# UsbUartBridge.net
KiCad netlist of a schematic drawn in EAGLE
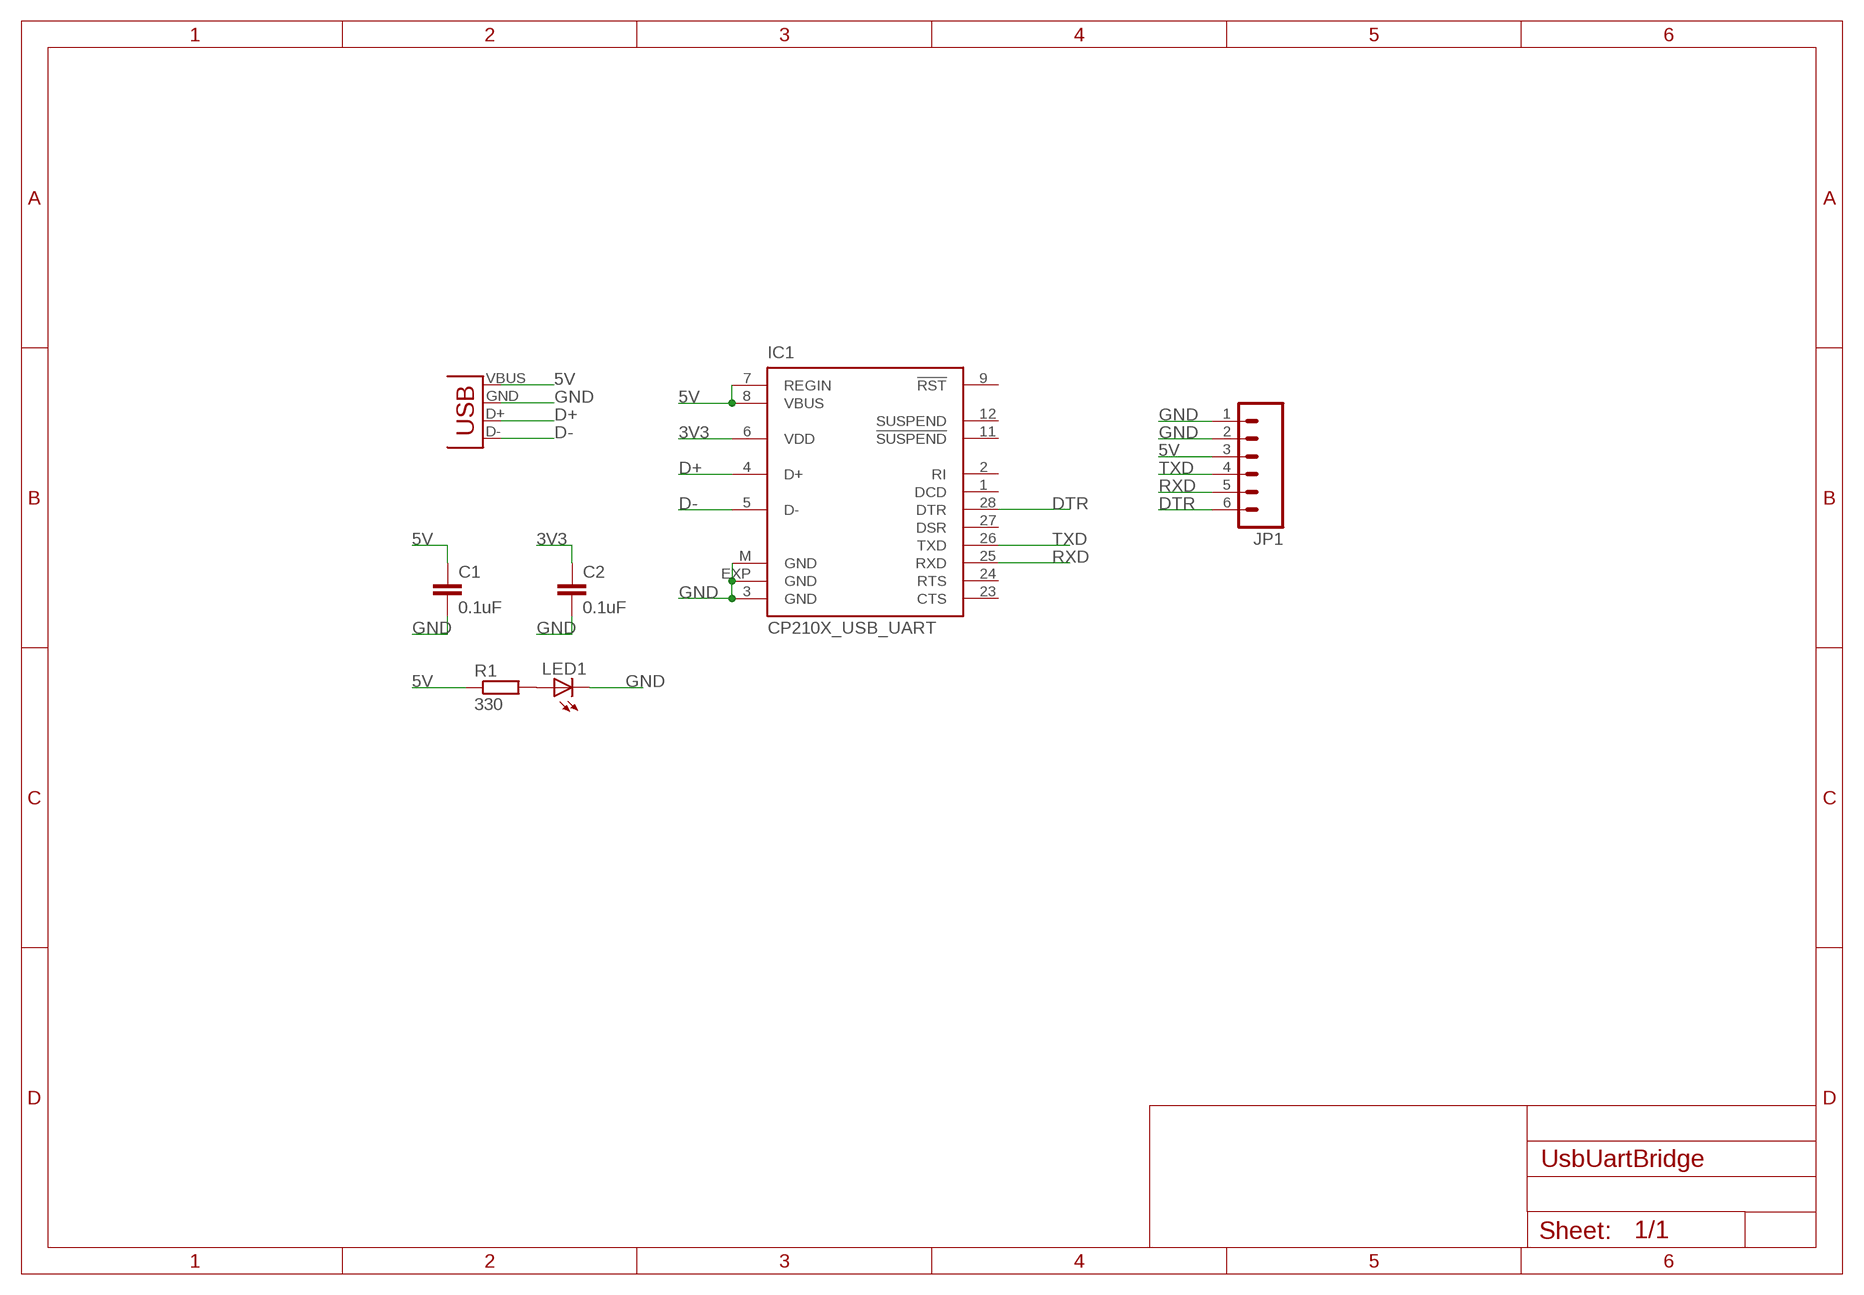
[diagram p0: schematic, sheet 1]

(export (version "E")
  (design (tool "Eeschema 10.0.6"))
  (components
    (comp (ref "C1")
      (value "0.1uF")
      (footprint "eagle-import:C025-024X044")
      (libsource (lib "eagle-import") (part "C-EU025-024X044"))
    )
    (comp (ref "C2")
      (value "0.1uF")
      (footprint "eagle-import:C025-024X044")
      (libsource (lib "eagle-import") (part "C-EU025-024X044"))
    )
    (comp (ref "IC1")
      (value "CP210X_USB_UART")
      (footprint "eagle-import:MLP28")
      (libsource (lib "eagle-import") (part "CP210X_USB_UART"))
    )
    (comp (ref "JP1")
      (value "M06SIP")
      (footprint "eagle-import:1X06")
      (libsource (lib "eagle-import") (part "M06SIP"))
    )
    (comp (ref "LED1")
      (value "LED3MM")
      (footprint "eagle-import:LED3MM")
      (libsource (lib "eagle-import") (part "LED3MM"))
    )
    (comp (ref "R1")
      (value "330")
      (footprint "eagle-import:0204_7")
      (libsource (lib "eagle-import") (part "R-EU_0204/7"))
    )
    (comp (ref "X1")
      (value "USB-A-H")
      (footprint "eagle-import:USB-A-H")
      (libsource (lib "eagle-import") (part "USB-A-H"))
    )
  )
  (nets
    (net (code "1") (name "/3V3") (class "Default")
      (node (ref "C2") (pin "1") (pinfunction "1_1") (pintype "passive"))
      (node (ref "IC1") (pin "6") (pinfunction "VDD_6") (pintype "power_in"))
    )
    (net (code "2") (name "/5V") (class "Default")
      (node (ref "C1") (pin "1") (pinfunction "1_1") (pintype "passive"))
      (node (ref "IC1") (pin "7") (pinfunction "REGIN_7") (pintype "passive"))
      (node (ref "IC1") (pin "8") (pinfunction "VBUS_8") (pintype "input"))
      (node (ref "JP1") (pin "3") (pinfunction "3_3") (pintype "passive"))
      (node (ref "R1") (pin "1") (pinfunction "1_1") (pintype "passive"))
      (node (ref "X1") (pin "VBUS") (pinfunction "GND_VBUS") (pintype "bidirectional"))
    )
    (net (code "3") (name "/D+") (class "Default")
      (node (ref "IC1") (pin "4") (pinfunction "D+_4") (pintype "bidirectional"))
      (node (ref "X1") (pin "D+") (pinfunction "D-_D+") (pintype "bidirectional"))
    )
    (net (code "4") (name "/D-") (class "Default")
      (node (ref "IC1") (pin "5") (pinfunction "D-_5") (pintype "bidirectional"))
      (node (ref "X1") (pin "D-") (pinfunction "D+_D-") (pintype "bidirectional"))
    )
    (net (code "5") (name "/DTR") (class "Default")
      (node (ref "IC1") (pin "28") (pinfunction "DTR_28") (pintype "output"))
      (node (ref "JP1") (pin "6") (pinfunction "6_6") (pintype "passive"))
    )
    (net (code "6") (name "/GND") (class "Default")
      (node (ref "C1") (pin "2") (pinfunction "2_2") (pintype "passive"))
      (node (ref "C2") (pin "2") (pinfunction "2_2") (pintype "passive"))
      (node (ref "IC1") (pin "3") (pinfunction "GND_3") (pintype "power_in"))
      (node (ref "IC1") (pin "EXP") (pinfunction "GND_EXP") (pintype "power_in"))
      (node (ref "IC1") (pin "M") (pinfunction "GND_M") (pintype "power_in"))
      (node (ref "JP1") (pin "1") (pinfunction "1_1") (pintype "passive"))
      (node (ref "JP1") (pin "2") (pinfunction "2_2") (pintype "passive"))
      (node (ref "LED1") (pin "K") (pinfunction "C_K") (pintype "passive"))
      (node (ref "X1") (pin "GND") (pinfunction "VBUS_GND") (pintype "bidirectional"))
    )
    (net (code "7") (name "/RXD") (class "Default")
      (node (ref "IC1") (pin "25") (pinfunction "RXD_25") (pintype "input"))
      (node (ref "JP1") (pin "5") (pinfunction "5_5") (pintype "passive"))
    )
    (net (code "8") (name "/TXD") (class "Default")
      (node (ref "IC1") (pin "26") (pinfunction "TXD_26") (pintype "output"))
      (node (ref "JP1") (pin "4") (pinfunction "4_4") (pintype "passive"))
    )
    (net (code "9") (name "Net-(LED1-PadA)") (class "Default")
      (node (ref "LED1") (pin "A") (pinfunction "A_A") (pintype "passive"))
      (node (ref "R1") (pin "2") (pinfunction "2_2") (pintype "passive"))
    )
    (net (code "10") (name "unconnected-(IC1-CTS-Pad23)") (class "Default")
      (node (ref "IC1") (pin "23") (pinfunction "CTS_23") (pintype "input"))
    )
    (net (code "11") (name "unconnected-(IC1-DCD-Pad1)") (class "Default")
      (node (ref "IC1") (pin "1") (pinfunction "DCD_1") (pintype "input"))
    )
    (net (code "12") (name "unconnected-(IC1-DSR-Pad27)") (class "Default")
      (node (ref "IC1") (pin "27") (pinfunction "DSR_27") (pintype "input"))
    )
    (net (code "13") (name "unconnected-(IC1-RI-Pad2)") (class "Default")
      (node (ref "IC1") (pin "2") (pinfunction "RI_2") (pintype "input"))
    )
    (net (code "14") (name "unconnected-(IC1-RTS-Pad24)") (class "Default")
      (node (ref "IC1") (pin "24") (pinfunction "RTS_24") (pintype "output"))
    )
    (net (code "15") (name "unconnected-(IC1-SUSPEND-Pad12)") (class "Default")
      (node (ref "IC1") (pin "12") (pinfunction "SUSPEND_12") (pintype "output"))
    )
    (net (code "16") (name "unconnected-(IC1-~{RST}-Pad9)") (class "Default")
      (node (ref "IC1") (pin "9") (pinfunction "~{RST}_9") (pintype "bidirectional"))
    )
    (net (code "17") (name "unconnected-(IC1-~{SUSPEND}-Pad11)") (class "Default")
      (node (ref "IC1") (pin "11") (pinfunction "~{SUSPEND}_11") (pintype "output"))
    )
  )
)
